# smc2.net
KiCad netlist of a schematic drawn in EAGLE
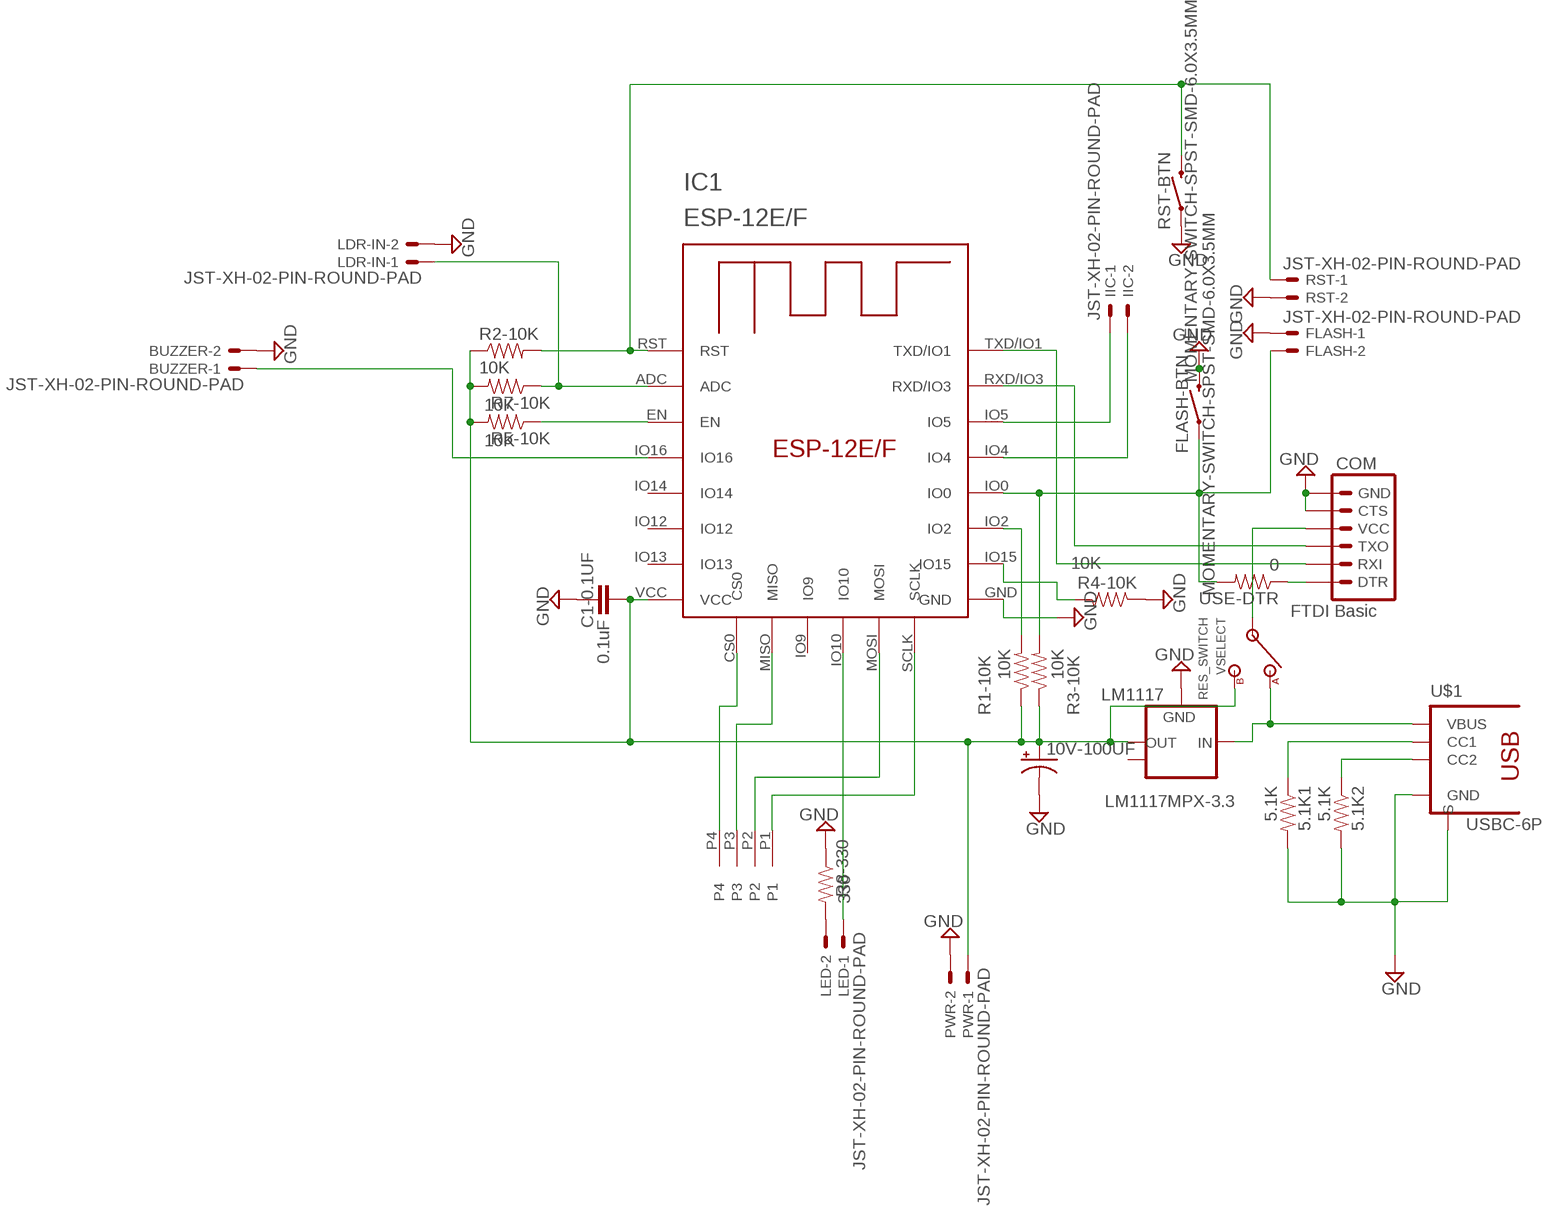
[diagram p0: schematic, sheet 1]

(export (version "E")
  (design (tool "Eeschema 10.0.6"))
  (components
    (comp (ref "5.1K1")
      (value "5.1K")
      (footprint "eagle-import:0603-RES")
      (libsource (lib "eagle-import") (part "RESISTOR0603-RES"))
    )
    (comp (ref "5.1K2")
      (value "5.1K")
      (footprint "eagle-import:0603-RES")
      (libsource (lib "eagle-import") (part "RESISTOR0603-RES"))
    )
    (comp (ref "10V-100UF")
      (value "CPOL-USA/3216-18W")
      (footprint "eagle-import:A_3216-18W")
      (libsource (lib "eagle-import") (part "CPOL-USA/3216-18W"))
    )
    (comp (ref "BUZZER")
      (value "JST-XH-02-PIN-ROUND-PAD")
      (footprint "eagle-import:JST-XH-02-PACKAGE-ROUND-PAD")
      (libsource (lib "eagle-import") (part "JST-XH-02-PIN-ROUND-PAD"))
    )
    (comp (ref "C1-0.1UF")
      (value "0.1uF")
      (footprint "eagle-import:0603-CAP")
      (libsource (lib "eagle-import") (part "CAP0603-CAP"))
    )
    (comp (ref "COM")
      (value "FTDI Basic")
      (footprint "eagle-import:1X06")
      (libsource (lib "eagle-import") (part "ARDUINO_SERIAL_PROGRAMPTH"))
    )
    (comp (ref "FLASH")
      (value "JST-XH-02-PIN-ROUND-PAD")
      (footprint "eagle-import:JST-XH-02-PACKAGE-ROUND-PAD")
      (libsource (lib "eagle-import") (part "JST-XH-02-PIN-ROUND-PAD"))
    )
    (comp (ref "FLASH-BTN")
      (value "MOMENTARY-SWITCH-SPST-SMD-6.0X3.5MM")
      (footprint "eagle-import:TACTILE_SWITCH_SMD_6.0X3.5MM")
      (libsource (lib "eagle-import") (part "MOMENTARY-SWITCH-SPST-SMD-6.0X3.5MM"))
    )
    (comp (ref "IC1")
      (value "ESP-12E/F")
      (footprint "eagle-import:ESP-12E")
      (libsource (lib "eagle-import") (part "ESP-12E/F"))
    )
    (comp (ref "IIC")
      (value "JST-XH-02-PIN-ROUND-PAD")
      (footprint "eagle-import:JST-XH-02-PACKAGE-ROUND-PAD")
      (libsource (lib "eagle-import") (part "JST-XH-02-PIN-ROUND-PAD"))
    )
    (comp (ref "LDR-IN")
      (value "JST-XH-02-PIN-ROUND-PAD")
      (footprint "eagle-import:JST-XH-02-PACKAGE-ROUND-PAD")
      (libsource (lib "eagle-import") (part "JST-XH-02-PIN-ROUND-PAD"))
    )
    (comp (ref "LED")
      (value "JST-XH-02-PIN-ROUND-PAD")
      (footprint "eagle-import:JST-XH-02-PACKAGE-ROUND-PAD")
      (libsource (lib "eagle-import") (part "JST-XH-02-PIN-ROUND-PAD"))
    )
    (comp (ref "LM1117")
      (value "LM1117MPX-3.3")
      (footprint "eagle-import:SOT223")
      (libsource (lib "eagle-import") (part "LM1117MPX-3.3"))
    )
    (comp (ref "PWR")
      (value "JST-XH-02-PIN-ROUND-PAD")
      (footprint "eagle-import:JST-XH-02-PACKAGE-ROUND-PAD")
      (libsource (lib "eagle-import") (part "JST-XH-02-PIN-ROUND-PAD"))
    )
    (comp (ref "R1-10K")
      (value "10K")
      (footprint "eagle-import:0603-RES")
      (libsource (lib "eagle-import") (part "RESISTOR0603-RES"))
    )
    (comp (ref "R2-10K")
      (value "10K")
      (footprint "eagle-import:0603-RES")
      (libsource (lib "eagle-import") (part "RESISTOR0603-RES"))
    )
    (comp (ref "R3-10K")
      (value "10K")
      (footprint "eagle-import:0603-RES")
      (libsource (lib "eagle-import") (part "RESISTOR0603-RES"))
    )
    (comp (ref "R4-10K")
      (value "10K")
      (footprint "eagle-import:0603-RES")
      (libsource (lib "eagle-import") (part "RESISTOR0603-RES"))
    )
    (comp (ref "R5-10K")
      (value "10K")
      (footprint "eagle-import:0603-RES")
      (libsource (lib "eagle-import") (part "RESISTOR0603-RES"))
    )
    (comp (ref "R7-10K")
      (value "10K")
      (footprint "eagle-import:0603-RES")
      (libsource (lib "eagle-import") (part "RESISTOR0603-RES"))
    )
    (comp (ref "R8-330")
      (value "330")
      (footprint "eagle-import:0603-RES")
      (libsource (lib "eagle-import") (part "RESISTOR0603-RES"))
    )
    (comp (ref "RST")
      (value "JST-XH-02-PIN-ROUND-PAD")
      (footprint "eagle-import:JST-XH-02-PACKAGE-ROUND-PAD")
      (libsource (lib "eagle-import") (part "JST-XH-02-PIN-ROUND-PAD"))
    )
    (comp (ref "RST-BTN")
      (value "MOMENTARY-SWITCH-SPST-SMD-6.0X3.5MM")
      (footprint "eagle-import:TACTILE_SWITCH_SMD_6.0X3.5MM")
      (libsource (lib "eagle-import") (part "MOMENTARY-SWITCH-SPST-SMD-6.0X3.5MM"))
    )
    (comp (ref "U$1")
      (value "USBC-6P")
      (footprint "eagle-import:USCX-06FX-XXMX-01")
      (libsource (lib "eagle-import") (part "USBC-6P"))
    )
    (comp (ref "U$3")
      (value "4PIN")
      (footprint "eagle-import:4PIN")
      (libsource (lib "eagle-import") (part "4PIN"))
    )
    (comp (ref "USE-DTR")
      (value "0")
      (footprint "eagle-import:0603-RES")
      (libsource (lib "eagle-import") (part "RESISTOR0603-RES"))
    )
    (comp (ref "VSELECT")
      (value "RES_SWITCH")
      (footprint "eagle-import:RES_SWITCH")
      (libsource (lib "eagle-import") (part "RES_SWITCH"))
    )
  )
  (nets
    (net (code "1") (name "GND") (class "Default")
      (node (ref "10V-100UF") (pin "-") (pinfunction "-_-") (pintype "passive"))
      (node (ref "5.1K1") (pin "2") (pinfunction "2_2") (pintype "passive"))
      (node (ref "5.1K2") (pin "2") (pinfunction "2_2") (pintype "passive"))
      (node (ref "BUZZER") (pin "2") (pinfunction "S_2") (pintype "passive"))
      (node (ref "C1-0.1UF") (pin "2") (pinfunction "2_2") (pintype "passive"))
      (node (ref "COM") (pin "5") (pinfunction "CTS_5") (pintype "passive"))
      (node (ref "COM") (pin "6") (pinfunction "GND_6") (pintype "passive"))
      (node (ref "FLASH") (pin "1") (pinfunction "S_1") (pintype "passive"))
      (node (ref "FLASH-BTN") (pin "2") (pinfunction "2_2") (pintype "passive"))
      (node (ref "IC1") (pin "GND") (pinfunction "GND_GND") (pintype "power_in"))
      (node (ref "LDR-IN") (pin "2") (pinfunction "S_2") (pintype "passive"))
      (node (ref "LM1117") (pin "1") (pinfunction "GND_1") (pintype "input"))
      (node (ref "PWR") (pin "2") (pinfunction "S_2") (pintype "passive"))
      (node (ref "R4-10K") (pin "1") (pinfunction "1_1") (pintype "passive"))
      (node (ref "R8-330") (pin "1") (pinfunction "1_1") (pintype "passive"))
      (node (ref "RST") (pin "2") (pinfunction "S_2") (pintype "passive"))
      (node (ref "RST-BTN") (pin "1") (pinfunction "1_1") (pintype "passive"))
      (node (ref "U$1") (pin "GND1") (pinfunction "GND_GND1") (pintype "power_in"))
      (node (ref "U$1") (pin "GND2") (pinfunction "GND_GND2") (pintype "power_in"))
      (node (ref "U$1") (pin "SHIELD1") (pinfunction "S_SHIELD1") (pintype "passive"))
      (node (ref "U$1") (pin "SHIELD2") (pinfunction "S_SHIELD2") (pintype "passive"))
      (node (ref "U$1") (pin "SHIELD3") (pinfunction "S_SHIELD3") (pintype "passive"))
      (node (ref "U$1") (pin "SHIELD4") (pinfunction "S_SHIELD4") (pintype "passive"))
    )
    (net (code "2") (name "Net-(5.1K1-Pad1)") (class "Default")
      (node (ref "5.1K1") (pin "1") (pinfunction "1_1") (pintype "passive"))
      (node (ref "U$1") (pin "CC1") (pinfunction "CC1_CC1") (pintype "bidirectional"))
    )
    (net (code "3") (name "Net-(5.1K2-Pad1)") (class "Default")
      (node (ref "5.1K2") (pin "1") (pinfunction "1_1") (pintype "passive"))
      (node (ref "U$1") (pin "CC2") (pinfunction "CC2_CC2") (pintype "bidirectional"))
    )
    (net (code "4") (name "Net-(BUZZERA-S)") (class "Default")
      (node (ref "BUZZER") (pin "1") (pinfunction "S_1") (pintype "passive"))
      (node (ref "IC1") (pin "IO16") (pinfunction "IO16_IO16") (pintype "bidirectional"))
    )
    (net (code "5") (name "Net-(COM-DTR)") (class "Default")
      (node (ref "COM") (pin "1") (pinfunction "DTR_1") (pintype "passive"))
      (node (ref "USE-DTR") (pin "1") (pinfunction "1_1") (pintype "passive"))
    )
    (net (code "6") (name "Net-(COM-RXI)") (class "Default")
      (node (ref "COM") (pin "2") (pinfunction "RXI_2") (pintype "passive"))
      (node (ref "IC1") (pin "TXD/IO1") (pinfunction "TXD/IO1_TXD/IO1") (pintype "bidirectional"))
    )
    (net (code "7") (name "Net-(COM-TXO)") (class "Default")
      (node (ref "COM") (pin "3") (pinfunction "TXO_3") (pintype "passive"))
      (node (ref "IC1") (pin "RXD/IO3") (pinfunction "RXD/IO3_RXD/IO3") (pintype "bidirectional"))
    )
    (net (code "8") (name "Net-(COM-VCC)") (class "Default")
      (node (ref "COM") (pin "4") (pinfunction "VCC_4") (pintype "passive"))
      (node (ref "VSELECT") (pin "C") (pinfunction "IN_C") (pintype "bidirectional"))
    )
    (net (code "9") (name "Net-(FLASHB-S)") (class "Default")
      (node (ref "FLASH") (pin "2") (pinfunction "S_2") (pintype "passive"))
      (node (ref "FLASH-BTN") (pin "1") (pinfunction "1_1") (pintype "passive"))
      (node (ref "IC1") (pin "IO0") (pinfunction "IO0_IO0") (pintype "bidirectional"))
      (node (ref "R3-10K") (pin "2") (pinfunction "2_2") (pintype "passive"))
      (node (ref "USE-DTR") (pin "2") (pinfunction "2_2") (pintype "passive"))
    )
    (net (code "10") (name "Net-(IC1-PadCS0)") (class "Default")
      (node (ref "IC1") (pin "CS0") (pinfunction "CS0_CS0") (pintype "bidirectional"))
      (node (ref "U$3") (pin "P4") (pinfunction "P4_P4") (pintype "bidirectional"))
    )
    (net (code "11") (name "Net-(IC1-PadEN)") (class "Default")
      (node (ref "IC1") (pin "EN") (pinfunction "EN_EN") (pintype "bidirectional"))
      (node (ref "R5-10K") (pin "1") (pinfunction "1_1") (pintype "passive"))
    )
    (net (code "12") (name "Net-(IC1-PadIO2)") (class "Default")
      (node (ref "IC1") (pin "IO2") (pinfunction "IO2_IO2") (pintype "bidirectional"))
      (node (ref "R1-10K") (pin "2") (pinfunction "2_2") (pintype "passive"))
    )
    (net (code "13") (name "Net-(IC1-PadIO15)") (class "Default")
      (node (ref "IC1") (pin "IO15") (pinfunction "IO15_IO15") (pintype "bidirectional"))
      (node (ref "R4-10K") (pin "2") (pinfunction "2_2") (pintype "passive"))
    )
    (net (code "14") (name "Net-(IC1-PadMISO)") (class "Default")
      (node (ref "IC1") (pin "MISO") (pinfunction "MISO_MISO") (pintype "bidirectional"))
      (node (ref "U$3") (pin "P3") (pinfunction "P3_P3") (pintype "bidirectional"))
    )
    (net (code "15") (name "Net-(IC1-PadMOSI)") (class "Default")
      (node (ref "IC1") (pin "MOSI") (pinfunction "MOSI_MOSI") (pintype "bidirectional"))
      (node (ref "U$3") (pin "P2") (pinfunction "P2_P2") (pintype "bidirectional"))
    )
    (net (code "16") (name "Net-(IC1-PadSCLK)") (class "Default")
      (node (ref "IC1") (pin "SCLK") (pinfunction "SCLK_SCLK") (pintype "bidirectional"))
      (node (ref "U$3") (pin "P1") (pinfunction "P1_P1") (pintype "bidirectional"))
    )
    (net (code "17") (name "Net-(IICA-S)") (class "Default")
      (node (ref "IC1") (pin "IO5") (pinfunction "IO5_IO5") (pintype "bidirectional"))
      (node (ref "IIC") (pin "1") (pinfunction "S_1") (pintype "passive"))
    )
    (net (code "18") (name "Net-(IICB-S)") (class "Default")
      (node (ref "IC1") (pin "IO4") (pinfunction "IO4_IO4") (pintype "bidirectional"))
      (node (ref "IIC") (pin "2") (pinfunction "S_2") (pintype "passive"))
    )
    (net (code "19") (name "Net-(LDR-INA-S)") (class "Default")
      (node (ref "IC1") (pin "ADC") (pinfunction "ADC_ADC") (pintype "bidirectional"))
      (node (ref "LDR-IN") (pin "1") (pinfunction "S_1") (pintype "passive"))
      (node (ref "R7-10K") (pin "1") (pinfunction "1_1") (pintype "passive"))
    )
    (net (code "20") (name "Net-(LEDA-S)") (class "Default")
      (node (ref "IC1") (pin "IO10") (pinfunction "IO10_IO10") (pintype "bidirectional"))
      (node (ref "LED") (pin "1") (pinfunction "S_1") (pintype "passive"))
    )
    (net (code "21") (name "Net-(LEDB-S)") (class "Default")
      (node (ref "LED") (pin "2") (pinfunction "S_2") (pintype "passive"))
      (node (ref "R8-330") (pin "2") (pinfunction "2_2") (pintype "passive"))
    )
    (net (code "22") (name "Net-(LM1117-IN)") (class "Default")
      (node (ref "LM1117") (pin "3") (pinfunction "IN_3") (pintype "input"))
      (node (ref "U$1") (pin "VBUS1") (pinfunction "VBUS_VBUS1") (pintype "power_in"))
      (node (ref "U$1") (pin "VBUS2") (pinfunction "VBUS_VBUS2") (pintype "power_in"))
      (node (ref "VSELECT") (pin "A") (pinfunction "A_A") (pintype "bidirectional"))
    )
    (net (code "23") (name "Net-(LM1117-OUT)") (class "Default")
      (node (ref "10V-100UF") (pin "+") (pinfunction "+_+") (pintype "passive"))
      (node (ref "C1-0.1UF") (pin "1") (pinfunction "1_1") (pintype "passive"))
      (node (ref "IC1") (pin "VCC") (pinfunction "VCC_VCC") (pintype "power_in"))
      (node (ref "LM1117") (pin "2") (pinfunction "OUT_2") (pintype "passive"))
      (node (ref "PWR") (pin "1") (pinfunction "S_1") (pintype "passive"))
      (node (ref "R1-10K") (pin "1") (pinfunction "1_1") (pintype "passive"))
      (node (ref "R2-10K") (pin "1") (pinfunction "1_1") (pintype "passive"))
      (node (ref "R3-10K") (pin "1") (pinfunction "1_1") (pintype "passive"))
      (node (ref "R5-10K") (pin "2") (pinfunction "2_2") (pintype "passive"))
      (node (ref "R7-10K") (pin "2") (pinfunction "2_2") (pintype "passive"))
      (node (ref "VSELECT") (pin "B") (pinfunction "B_B") (pintype "bidirectional"))
    )
    (net (code "24") (name "Net-(RSTA-S)") (class "Default")
      (node (ref "IC1") (pin "RST") (pinfunction "RST_RST") (pintype "input"))
      (node (ref "R2-10K") (pin "2") (pinfunction "2_2") (pintype "passive"))
      (node (ref "RST") (pin "1") (pinfunction "S_1") (pintype "passive"))
      (node (ref "RST-BTN") (pin "2") (pinfunction "2_2") (pintype "passive"))
    )
    (net (code "25") (name "unconnected-(IC1-PadIO9)") (class "Default")
      (node (ref "IC1") (pin "IO9") (pinfunction "IO9_IO9") (pintype "bidirectional"))
    )
    (net (code "26") (name "unconnected-(IC1-PadIO12)") (class "Default")
      (node (ref "IC1") (pin "IO12") (pinfunction "IO12_IO12") (pintype "bidirectional"))
    )
    (net (code "27") (name "unconnected-(IC1-PadIO13)") (class "Default")
      (node (ref "IC1") (pin "IO13") (pinfunction "IO13_IO13") (pintype "bidirectional"))
    )
    (net (code "28") (name "unconnected-(IC1-PadIO14)") (class "Default")
      (node (ref "IC1") (pin "IO14") (pinfunction "IO14_IO14") (pintype "bidirectional"))
    )
    (net (code "29") (name "unconnected-(LM1117-OUT1-PadTAB)") (class "Default")
      (node (ref "LM1117") (pin "TAB") (pinfunction "OUT1_TAB") (pintype "passive"))
    )
  )
)
